# With_GPS.net
KiCad netlist of a schematic drawn in EAGLE
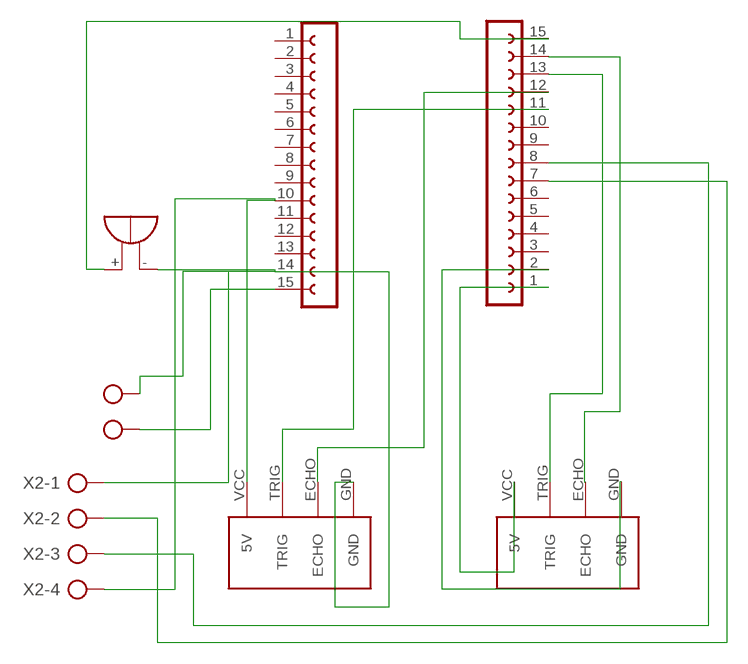
[diagram p0: schematic, sheet 1]

(export (version "E")
  (design (tool "Eeschema 10.0.6"))
  (components
    (comp (ref "J_ULTRASONIC_3")
      (value "HC-SR04")
      (footprint "eagle-import:HC-SR04_FOOTPRINT")
      (libsource (lib "eagle-import") (part "HC-SR04"))
    )
    (comp (ref "J_ULTRASONIC_4")
      (value "HC-SR04")
      (footprint "eagle-import:HC-SR04_FOOTPRINT")
      (libsource (lib "eagle-import") (part "HC-SR04"))
    )
    (comp (ref "SG2")
      (value "EB2505")
      (footprint "eagle-import:EB2505")
      (libsource (lib "eagle-import") (part "EB2505"))
    )
    (comp (ref "SV1")
      (value "FE15-1")
      (footprint "eagle-import:FE15")
      (libsource (lib "eagle-import") (part "FE15-1"))
    )
    (comp (ref "SV2")
      (value "FE15-1")
      (footprint "eagle-import:FE15")
      (libsource (lib "eagle-import") (part "FE15-1"))
    )
    (comp (ref "X1")
      (value "AK500/2-H")
      (footprint "eagle-import:AK500_2-H")
      (libsource (lib "eagle-import") (part "AK500/2-H"))
    )
    (comp (ref "X2")
      (value "AK300/4")
      (footprint "eagle-import:AK300_4")
      (libsource (lib "eagle-import") (part "AK300/4"))
    )
  )
  (nets
    (net (code "1") (name "Net-(J_ULTRASONIC_3-5V)") (class "Default")
      (node (ref "J_ULTRASONIC_3") (pin "VCC") (pinfunction "5V_VCC") (pintype "bidirectional"))
      (node (ref "SV1") (pin "1") (pinfunction "1_1") (pintype "passive"))
    )
    (net (code "2") (name "Net-(J_ULTRASONIC_3-PadECHO)") (class "Default")
      (node (ref "J_ULTRASONIC_3") (pin "ECHO") (pinfunction "ECHO_ECHO") (pintype "bidirectional"))
      (node (ref "SV1") (pin "14") (pinfunction "14_14") (pintype "passive"))
    )
    (net (code "3") (name "Net-(J_ULTRASONIC_3-PadGND)") (class "Default")
      (node (ref "J_ULTRASONIC_3") (pin "GND") (pinfunction "GND_GND") (pintype "bidirectional"))
      (node (ref "SV1") (pin "2") (pinfunction "2_2") (pintype "passive"))
    )
    (net (code "4") (name "Net-(J_ULTRASONIC_3-PadTRIG)") (class "Default")
      (node (ref "J_ULTRASONIC_3") (pin "TRIG") (pinfunction "TRIG_TRIG") (pintype "bidirectional"))
      (node (ref "SV1") (pin "13") (pinfunction "13_13") (pintype "passive"))
    )
    (net (code "5") (name "Net-(J_ULTRASONIC_4-5V)") (class "Default")
      (node (ref "J_ULTRASONIC_4") (pin "VCC") (pinfunction "5V_VCC") (pintype "bidirectional"))
      (node (ref "SV2") (pin "10") (pinfunction "10_10") (pintype "passive"))
      (node (ref "X2") (pin "4") (pinfunction "KL_4") (pintype "passive"))
    )
    (net (code "6") (name "Net-(J_ULTRASONIC_4-PadECHO)") (class "Default")
      (node (ref "J_ULTRASONIC_4") (pin "ECHO") (pinfunction "ECHO_ECHO") (pintype "bidirectional"))
      (node (ref "SV1") (pin "12") (pinfunction "12_12") (pintype "passive"))
    )
    (net (code "7") (name "Net-(J_ULTRASONIC_4-PadTRIG)") (class "Default")
      (node (ref "J_ULTRASONIC_4") (pin "TRIG") (pinfunction "TRIG_TRIG") (pintype "bidirectional"))
      (node (ref "SV1") (pin "11") (pinfunction "11_11") (pintype "passive"))
    )
    (net (code "8") (name "Net-(SG2-Pad+)") (class "Default")
      (node (ref "SG2") (pin "+") (pinfunction "+_+") (pintype "passive"))
      (node (ref "SV1") (pin "15") (pinfunction "15_15") (pintype "passive"))
    )
    (net (code "9") (name "Net-(X1A-KL)") (class "Default")
      (node (ref "J_ULTRASONIC_4") (pin "GND") (pinfunction "GND_GND") (pintype "bidirectional"))
      (node (ref "SG2") (pin "-") (pinfunction "-_-") (pintype "passive"))
      (node (ref "SV2") (pin "14") (pinfunction "14_14") (pintype "passive"))
      (node (ref "X1") (pin "1") (pinfunction "KL_1") (pintype "passive"))
      (node (ref "X2") (pin "1") (pinfunction "KL_1") (pintype "passive"))
    )
    (net (code "10") (name "Net-(X1B-KL)") (class "Default")
      (node (ref "SV2") (pin "15") (pinfunction "15_15") (pintype "passive"))
      (node (ref "X1") (pin "2") (pinfunction "KL_2") (pintype "passive"))
    )
    (net (code "11") (name "Net-(X2B-KL)") (class "Default")
      (node (ref "SV1") (pin "7") (pinfunction "7_7") (pintype "passive"))
      (node (ref "X2") (pin "2") (pinfunction "KL_2") (pintype "passive"))
    )
    (net (code "12") (name "Net-(X2C-KL)") (class "Default")
      (node (ref "SV1") (pin "8") (pinfunction "8_8") (pintype "passive"))
      (node (ref "X2") (pin "3") (pinfunction "KL_3") (pintype "passive"))
    )
    (net (code "13") (name "unconnected-(SV1-Pad3)") (class "Default")
      (node (ref "SV1") (pin "3") (pinfunction "3_3") (pintype "passive"))
    )
    (net (code "14") (name "unconnected-(SV1-Pad4)") (class "Default")
      (node (ref "SV1") (pin "4") (pinfunction "4_4") (pintype "passive"))
    )
    (net (code "15") (name "unconnected-(SV1-Pad5)") (class "Default")
      (node (ref "SV1") (pin "5") (pinfunction "5_5") (pintype "passive"))
    )
    (net (code "16") (name "unconnected-(SV1-Pad6)") (class "Default")
      (node (ref "SV1") (pin "6") (pinfunction "6_6") (pintype "passive"))
    )
    (net (code "17") (name "unconnected-(SV1-Pad9)") (class "Default")
      (node (ref "SV1") (pin "9") (pinfunction "9_9") (pintype "passive"))
    )
    (net (code "18") (name "unconnected-(SV1-Pad10)") (class "Default")
      (node (ref "SV1") (pin "10") (pinfunction "10_10") (pintype "passive"))
    )
    (net (code "19") (name "unconnected-(SV2-Pad1)") (class "Default")
      (node (ref "SV2") (pin "1") (pinfunction "1_1") (pintype "passive"))
    )
    (net (code "20") (name "unconnected-(SV2-Pad2)") (class "Default")
      (node (ref "SV2") (pin "2") (pinfunction "2_2") (pintype "passive"))
    )
    (net (code "21") (name "unconnected-(SV2-Pad3)") (class "Default")
      (node (ref "SV2") (pin "3") (pinfunction "3_3") (pintype "passive"))
    )
    (net (code "22") (name "unconnected-(SV2-Pad4)") (class "Default")
      (node (ref "SV2") (pin "4") (pinfunction "4_4") (pintype "passive"))
    )
    (net (code "23") (name "unconnected-(SV2-Pad5)") (class "Default")
      (node (ref "SV2") (pin "5") (pinfunction "5_5") (pintype "passive"))
    )
    (net (code "24") (name "unconnected-(SV2-Pad6)") (class "Default")
      (node (ref "SV2") (pin "6") (pinfunction "6_6") (pintype "passive"))
    )
    (net (code "25") (name "unconnected-(SV2-Pad7)") (class "Default")
      (node (ref "SV2") (pin "7") (pinfunction "7_7") (pintype "passive"))
    )
    (net (code "26") (name "unconnected-(SV2-Pad8)") (class "Default")
      (node (ref "SV2") (pin "8") (pinfunction "8_8") (pintype "passive"))
    )
    (net (code "27") (name "unconnected-(SV2-Pad9)") (class "Default")
      (node (ref "SV2") (pin "9") (pinfunction "9_9") (pintype "passive"))
    )
    (net (code "28") (name "unconnected-(SV2-Pad11)") (class "Default")
      (node (ref "SV2") (pin "11") (pinfunction "11_11") (pintype "passive"))
    )
    (net (code "29") (name "unconnected-(SV2-Pad12)") (class "Default")
      (node (ref "SV2") (pin "12") (pinfunction "12_12") (pintype "passive"))
    )
    (net (code "30") (name "unconnected-(SV2-Pad13)") (class "Default")
      (node (ref "SV2") (pin "13") (pinfunction "13_13") (pintype "passive"))
    )
  )
)
